# Power-Supply.net
KiCad netlist of a schematic drawn in Altium Designer
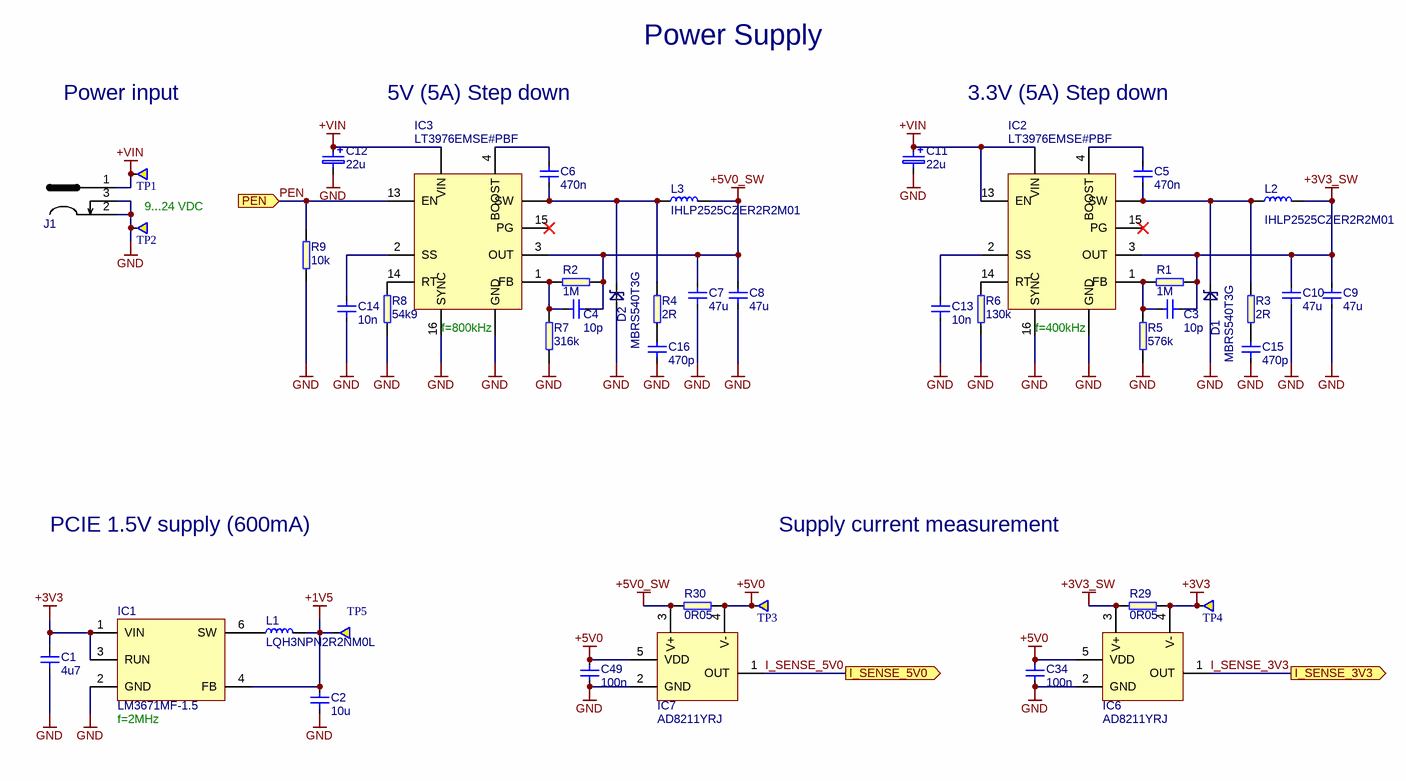
[diagram p0: Power-Supply.SchDoc]

(export (version "E")
  (design (tool "Eeschema 10.0.6"))
  (components
    (comp (ref "C1")
      (value "4u7")
      (footprint "0402")
      (description "MLCC SMT Capacitor 4.7uF 0402")
      (fields (field (name "MANUFACTURER") "MURATA") (field (name "PART NUMBER") "C_4u7_0402"))
      (libsource (lib "TK1Baseboard") (part "C_4u7_0402"))
    )
    (comp (ref "C2")
      (value "10u")
      (footprint "0603")
      (description "MLCC SMT Capacitor 10uF 0603")
      (fields (field (name "MANUFACTURER") "Walsin") (field (name "PART NUMBER") "C_10u_0603"))
      (libsource (lib "TK1Baseboard") (part "C_10u_0603"))
    )
    (comp (ref "C3")
      (value "10p")
      (footprint "0402")
      (description "MLCC SMT Capacitor 10pF 0402")
      (fields (field (name "MANUFACTURER") "MULTICOMP") (field (name "PART NUMBER") "C_10p_0402"))
      (libsource (lib "TK1Baseboard") (part "C_10p_0402"))
    )
    (comp (ref "C4")
      (value "10p")
      (footprint "0402")
      (description "MLCC SMT Capacitor 10pF 0402")
      (fields (field (name "MANUFACTURER") "MULTICOMP") (field (name "PART NUMBER") "C_10p_0402"))
      (libsource (lib "TK1Baseboard") (part "C_10p_0402"))
    )
    (comp (ref "C5")
      (value "470n")
      (footprint "0402")
      (description "MLCC SMT Capacitor 470n 0402")
      (fields (field (name "MANUFACTURER") "TDK") (field (name "PART NUMBER") "C_470n_0402"))
      (libsource (lib "TK1Baseboard") (part "C_470n_0402"))
    )
    (comp (ref "C6")
      (value "470n")
      (footprint "0402")
      (description "MLCC SMT Capacitor 470n 0402")
      (fields (field (name "MANUFACTURER") "TDK") (field (name "PART NUMBER") "C_470n_0402"))
      (libsource (lib "TK1Baseboard") (part "C_470n_0402"))
    )
    (comp (ref "C7")
      (value "47u")
      (footprint "1206")
      (description "MLCC SMT Capacitor 47uF 1206")
      (fields (field (name "MANUFACTURER") "MURATA") (field (name "PART NUMBER") "C_47u_1206"))
      (libsource (lib "TK1Baseboard") (part "C_47u_1206"))
    )
    (comp (ref "C8")
      (value "47u")
      (footprint "1206")
      (description "MLCC SMT Capacitor 47uF 1206")
      (fields (field (name "MANUFACTURER") "MURATA") (field (name "PART NUMBER") "C_47u_1206"))
      (libsource (lib "TK1Baseboard") (part "C_47u_1206"))
    )
    (comp (ref "C9")
      (value "47u")
      (footprint "1206")
      (description "MLCC SMT Capacitor 47uF 1206")
      (fields (field (name "MANUFACTURER") "MURATA") (field (name "PART NUMBER") "C_47u_1206"))
      (libsource (lib "TK1Baseboard") (part "C_47u_1206"))
    )
    (comp (ref "C10")
      (value "47u")
      (footprint "1206")
      (description "MLCC SMT Capacitor 47uF 1206")
      (fields (field (name "MANUFACTURER") "MURATA") (field (name "PART NUMBER") "C_47u_1206"))
      (libsource (lib "TK1Baseboard") (part "C_47u_1206"))
    )
    (comp (ref "C11")
      (value "22u")
      (footprint "KEMET_C")
      (description "Tantalum SMT Capacitor 22uF Case KEMET_C")
      (fields (field (name "PART NUMBER") "C_22u_KEMET_C") (field (name "MANUFACTURER") "KEMET"))
      (libsource (lib "TK1Baseboard") (part "C_22u_KEMET_C"))
    )
    (comp (ref "C12")
      (value "22u")
      (footprint "KEMET_C")
      (description "Tantalum SMT Capacitor 22uF Case KEMET_C")
      (fields (field (name "PART NUMBER") "C_22u_KEMET_C") (field (name "MANUFACTURER") "KEMET"))
      (libsource (lib "TK1Baseboard") (part "C_22u_KEMET_C"))
    )
    (comp (ref "C13")
      (value "10n")
      (footprint "0402")
      (description "MLCC SMT Capacitor 10 nF 0402")
      (fields (field (name "MANUFACTURER") "AVX") (field (name "PART NUMBER") "C_10n_0402"))
      (libsource (lib "TK1Baseboard") (part "C_10n_0402"))
    )
    (comp (ref "C14")
      (value "10n")
      (footprint "0402")
      (description "MLCC SMT Capacitor 10 nF 0402")
      (fields (field (name "MANUFACTURER") "AVX") (field (name "PART NUMBER") "C_10n_0402"))
      (libsource (lib "TK1Baseboard") (part "C_10n_0402"))
    )
    (comp (ref "C15")
      (value "470p")
      (footprint "0402")
      (description "MLCC SMT Capacitor 470pF 0402")
      (fields (field (name "MANUFACTURER") "MULTICOMP") (field (name "PART NUMBER") "C_470p_0402"))
      (libsource (lib "TK1Baseboard") (part "C_470p_0402"))
    )
    (comp (ref "C16")
      (value "470p")
      (footprint "0402")
      (description "MLCC SMT Capacitor 470pF 0402")
      (fields (field (name "MANUFACTURER") "MULTICOMP") (field (name "PART NUMBER") "C_470p_0402"))
      (libsource (lib "TK1Baseboard") (part "C_470p_0402"))
    )
    (comp (ref "C34")
      (value "100n")
      (footprint "0402")
      (description "MLCC SMT Capacitor 100n 0402")
      (fields (field (name "MANUFACTURER") "TDK") (field (name "PART NUMBER") "C_100n_0402"))
      (libsource (lib "TK1Baseboard") (part "C_100n_0402"))
    )
    (comp (ref "C49")
      (value "100n")
      (footprint "0402")
      (description "MLCC SMT Capacitor 100n 0402")
      (fields (field (name "MANUFACTURER") "TDK") (field (name "PART NUMBER") "C_100n_0402"))
      (libsource (lib "TK1Baseboard") (part "C_100n_0402"))
    )
    (comp (ref "D1")
      (value "MBRS540T3G")
      (footprint "SMC-403-03")
      (description "ON SEMICONDUCTOR  MBRS540T3G  Rectifier Diode, Single, 40 V, 5 A, 500 mV, 190 A, 150 °C")
      (fields (field (name "MANUFACTURER") "ON SEMICONDUCTOR"))
      (libsource (lib "TK1Baseboard") (part "MBRS540T3G"))
    )
    (comp (ref "D2")
      (value "MBRS540T3G")
      (footprint "SMC-403-03")
      (description "ON SEMICONDUCTOR  MBRS540T3G  Rectifier Diode, Single, 40 V, 5 A, 500 mV, 190 A, 150 °C")
      (fields (field (name "MANUFACTURER") "ON SEMICONDUCTOR"))
      (libsource (lib "TK1Baseboard") (part "MBRS540T3G"))
    )
    (comp (ref "IC1")
      (value "LM3671MF-1.5")
      (footprint "SOT23-5N")
      (description "DC/DC Buck Converter")
      (fields (field (name "MANUFACTURER") "TEXAS INSTRUMENTS") (field (name "MPN") "LM3671MF-1.5/NOPB"))
      (libsource (lib "TK1Baseboard") (part "LM3671"))
    )
    (comp (ref "IC2")
      (value "LT3976EMSE#PBF")
      (footprint "LT3976EMSE")
      (description "LINEAR TECHNOLOGY  LT3976EMSE#PBF  DC-DC CONVERTER, 2MHZ, 5A, MSOP-16")
      (fields (field (name "MANUFACTURER") "LINEAR TECHNOLOGY"))
      (libsource (lib "TK1Baseboard") (part "LT3976"))
    )
    (comp (ref "IC3")
      (value "LT3976EMSE#PBF")
      (footprint "LT3976EMSE")
      (description "LINEAR TECHNOLOGY  LT3976EMSE#PBF  DC-DC CONVERTER, 2MHZ, 5A, MSOP-16")
      (fields (field (name "MANUFACTURER") "LINEAR TECHNOLOGY"))
      (libsource (lib "TK1Baseboard") (part "LT3976"))
    )
    (comp (ref "IC6")
      (value "AD8211YRJ")
      (footprint "SOT23-5")
      (description "Current Sense Amplifier, High Voltage, 1 Amplifier, SOT-23, 5 Pins, -40 °C, 125 °C")
      (fields (field (name "MANUFACTURER") "ANALOG DEVICES"))
      (libsource (lib "TK1Baseboard") (part "AD8211YRJ"))
    )
    (comp (ref "IC7")
      (value "AD8211YRJ")
      (footprint "SOT23-5")
      (description "Current Sense Amplifier, High Voltage, 1 Amplifier, SOT-23, 5 Pins, -40 °C, 125 °C")
      (fields (field (name "MANUFACTURER") "ANALOG DEVICES"))
      (libsource (lib "TK1Baseboard") (part "AD8211YRJ"))
    )
    (comp (ref "J1")
      (value "694106106102")
      (footprint "694106106102")
      (description "DC Power Jack Right Angled SMT with 4 soldering pads & pegs WR-DC")
      (fields (field (name "PART NUMBER") "WE-694106106102") (field (name "MANUFACTURER") "WURTH ELEKTRONIK"))
      (libsource (lib "TK1Baseboard") (part "DC_SOCKET_2"))
    )
    (comp (ref "L1")
      (value "LQH3NPN2R2NM0L")
      (footprint "LQH3NPN2R2NM")
      (description "INDUCTOR, 2.2 µH, ± 30%, 1212, 90 MHz, 0.073 ohm")
      (fields (field (name "MANUFACTURER") "MURATA"))
      (libsource (lib "TK1Baseboard") (part "LQH3NPN2R2NM0L"))
    )
    (comp (ref "L2")
      (value "IHLP2525CZER2R2M01")
      (footprint "IHLP-2525CZ-01")
      (fields (field (name "MANUFACTURER") "VISHAY") (field (name "MPN") "IHLP2525CZER3R3M01"))
      (libsource (lib "TK1Baseboard") (part "Inductor SMT"))
    )
    (comp (ref "L3")
      (value "IHLP2525CZER2R2M01")
      (footprint "IHLP-2525CZ-01")
      (fields (field (name "MANUFACTURER") "VISHAY") (field (name "MPN") "IHLP2525CZER3R3M01"))
      (libsource (lib "TK1Baseboard") (part "Inductor SMT"))
    )
    (comp (ref "R1")
      (value "1M")
      (footprint "0402")
      (description "RES, 1M, 0402")
      (fields (field (name "MANUFACTURER") "VISHAY") (field (name "PART NUMBER") "R_1M_0402"))
      (libsource (lib "TK1Baseboard") (part "R_1M_0402"))
    )
    (comp (ref "R2")
      (value "1M")
      (footprint "0402")
      (description "RES, 1M, 0402")
      (fields (field (name "MANUFACTURER") "VISHAY") (field (name "PART NUMBER") "R_1M_0402"))
      (libsource (lib "") (part "R_1M_0402_1"))
    )
    (comp (ref "R3")
      (value "2R")
      (footprint "0402")
      (description "RES, 2R, 0402")
      (fields (field (name "MANUFACTURER") "YAGEO") (field (name "PART NUMBER") "R_2R_0402"))
      (libsource (lib "TK1Baseboard") (part "R_2R_0402"))
    )
    (comp (ref "R4")
      (value "2R")
      (footprint "0402")
      (description "RES, 2R, 0402")
      (fields (field (name "MANUFACTURER") "YAGEO") (field (name "PART NUMBER") "R_2R_0402"))
      (libsource (lib "TK1Baseboard") (part "R_2R_0402"))
    )
    (comp (ref "R5")
      (value "576k")
      (footprint "0402")
      (description "RES, 576k, 0402")
      (fields (field (name "MANUFACTURER") "MULTICOMP") (field (name "PART NUMBER") "R_576k_0402"))
      (libsource (lib "TK1Baseboard") (part "R_576k_0402"))
    )
    (comp (ref "R6")
      (value "130k")
      (footprint "0402")
      (description "RES, 130k, 0402")
      (fields (field (name "MANUFACTURER") "MULTICOMP") (field (name "PART NUMBER") "R_130k_0402"))
      (libsource (lib "TK1Baseboard") (part "R_130k_0402"))
    )
    (comp (ref "R7")
      (value "316k")
      (footprint "0402")
      (description "RES, 316k, 0402")
      (fields (field (name "MANUFACTURER") "VISHAY") (field (name "PART NUMBER") "R_316k_0402"))
      (libsource (lib "TK1Baseboard") (part "R_316k_0402"))
    )
    (comp (ref "R8")
      (value "54k9")
      (footprint "0402")
      (description "RES, 54k9, 0402")
      (fields (field (name "MANUFACTURER") "MULTICOMP") (field (name "PART NUMBER") "R_54k9_0402"))
      (libsource (lib "TK1Baseboard") (part "R_54k9_0402"))
    )
    (comp (ref "R9")
      (value "10k")
      (footprint "0402")
      (description "RES, 10k, 0402")
      (fields (field (name "MANUFACTURER") "MULTICOMP") (field (name "PART NUMBER") "R_10k_0402"))
      (libsource (lib "TK1Baseboard") (part "R_10k_0402"))
    )
    (comp (ref "R29")
      (value "0R05")
      (footprint "1206")
      (description "RES, 0R05, 1206")
      (fields (field (name "MANUFACTURER") "PANASONIC") (field (name "PART NUMBER") "R_0R05_1206"))
      (libsource (lib "TK1Baseboard") (part "R_0R05_1206"))
    )
    (comp (ref "R30")
      (value "0R05")
      (footprint "1206")
      (description "RES, 0R05, 1206")
      (fields (field (name "MANUFACTURER") "PANASONIC") (field (name "PART NUMBER") "R_0R05_1206"))
      (libsource (lib "TK1Baseboard") (part "R_0R05_1206"))
    )
    (comp (ref "TP1")
      (value "TP-R-1.5")
      (footprint "TP-R-1.5")
      (description "Testpad, round, 1.5mm")
      (libsource (lib "TK1Baseboard") (part "TP-R-1.5"))
    )
    (comp (ref "TP2")
      (value "TP-R-1.5")
      (footprint "TP-R-1.5")
      (description "Testpad, round, 1.5mm")
      (libsource (lib "TK1Baseboard") (part "TP-R-1.5"))
    )
    (comp (ref "TP3")
      (value "TP-R-1.5")
      (footprint "TP-R-1.5")
      (description "Testpad, round, 1.5mm")
      (libsource (lib "TK1Baseboard") (part "TP-R-1.5"))
    )
    (comp (ref "TP4")
      (value "TP-R-1.5")
      (footprint "TP-R-1.5")
      (description "Testpad, round, 1.5mm")
      (libsource (lib "TK1Baseboard") (part "TP-R-1.5"))
    )
    (comp (ref "TP5")
      (value "TP-R-1.5")
      (footprint "TP-R-1.5")
      (description "Testpad, round, 1.5mm")
      (libsource (lib "TK1Baseboard") (part "TP-R-1.5"))
    )
  )
  (nets
    (net (code "1") (name "+1V5") (class "Default")
      (node (ref "C2") (pin "2") (pinfunction "2_2") (pintype "passive"))
      (node (ref "IC1") (pin "4") (pinfunction "FB_4") (pintype "passive"))
      (node (ref "L1") (pin "2") (pintype "passive"))
      (node (ref "TP5") (pin "1") (pintype "passive"))
    )
    (net (code "2") (name "+3V3") (class "Default")
      (node (ref "C1") (pin "2") (pinfunction "2_2") (pintype "passive"))
      (node (ref "IC1") (pin "1") (pinfunction "VIN_1") (pintype "passive"))
      (node (ref "IC1") (pin "3") (pinfunction "RUN_3") (pintype "passive"))
      (node (ref "IC6") (pin "4") (pinfunction "V-_4") (pintype "passive"))
      (node (ref "R29") (pin "1") (pintype "passive"))
      (node (ref "TP4") (pin "1") (pintype "passive"))
    )
    (net (code "3") (name "+3V3_SW") (class "Default")
      (node (ref "C10") (pin "2") (pinfunction "2_2") (pintype "passive"))
      (node (ref "C3") (pin "1") (pinfunction "1_1") (pintype "passive"))
      (node (ref "C9") (pin "2") (pinfunction "2_2") (pintype "passive"))
      (node (ref "IC2") (pin "3") (pinfunction "OUT_3") (pintype "passive"))
      (node (ref "IC6") (pin "3") (pinfunction "V+_3") (pintype "passive"))
      (node (ref "L2") (pin "2") (pintype "passive"))
      (node (ref "R1") (pin "1") (pintype "passive"))
      (node (ref "R29") (pin "2") (pintype "passive"))
    )
    (net (code "4") (name "+5V0") (class "Default")
      (node (ref "C34") (pin "1") (pinfunction "1_1") (pintype "passive"))
      (node (ref "C49") (pin "1") (pinfunction "1_1") (pintype "passive"))
      (node (ref "IC6") (pin "5") (pinfunction "VDD_5") (pintype "passive"))
      (node (ref "IC7") (pin "4") (pinfunction "V-_4") (pintype "passive"))
      (node (ref "IC7") (pin "5") (pinfunction "VDD_5") (pintype "passive"))
      (node (ref "R30") (pin "1") (pintype "passive"))
      (node (ref "TP3") (pin "1") (pintype "passive"))
    )
    (net (code "5") (name "+5V0_SW") (class "Default")
      (node (ref "C4") (pin "1") (pinfunction "1_1") (pintype "passive"))
      (node (ref "C7") (pin "2") (pinfunction "2_2") (pintype "passive"))
      (node (ref "C8") (pin "2") (pinfunction "2_2") (pintype "passive"))
      (node (ref "IC3") (pin "3") (pinfunction "OUT_3") (pintype "passive"))
      (node (ref "IC7") (pin "3") (pinfunction "V+_3") (pintype "passive"))
      (node (ref "L3") (pin "2") (pintype "passive"))
      (node (ref "R2") (pin "1") (pintype "passive"))
      (node (ref "R30") (pin "2") (pintype "passive"))
    )
    (net (code "6") (name "+VIN") (class "Default")
      (node (ref "C11") (pin "1") (pinfunction "1_1") (pintype "passive"))
      (node (ref "C12") (pin "1") (pinfunction "1_1") (pintype "passive"))
      (node (ref "IC2") (pin "13") (pinfunction "EN_13") (pintype "passive"))
      (node (ref "IC2") (pin "VIN") (pinfunction "VIN_VIN") (pintype "passive"))
      (node (ref "IC3") (pin "VIN") (pinfunction "VIN_VIN") (pintype "passive"))
      (node (ref "J1") (pin "1") (pinfunction "1_1") (pintype "passive"))
      (node (ref "TP1") (pin "1") (pintype "passive"))
    )
    (net (code "7") (name "/I_SENSE_3V3") (class "Default")
      (node (ref "IC6") (pin "1") (pinfunction "OUT_1") (pintype "passive"))
    )
    (net (code "8") (name "/I_SENSE_5V0") (class "Default")
      (node (ref "IC7") (pin "1") (pinfunction "OUT_1") (pintype "passive"))
    )
    (net (code "9") (name "/PEN") (class "Default")
      (node (ref "IC3") (pin "13") (pinfunction "EN_13") (pintype "passive"))
      (node (ref "R9") (pin "2") (pintype "passive"))
    )
    (net (code "10") (name "GND") (class "Default")
      (node (ref "C1") (pin "1") (pinfunction "1_1") (pintype "passive"))
      (node (ref "C10") (pin "1") (pinfunction "1_1") (pintype "passive"))
      (node (ref "C11") (pin "2") (pinfunction "2_2") (pintype "passive"))
      (node (ref "C12") (pin "2") (pinfunction "2_2") (pintype "passive"))
      (node (ref "C13") (pin "1") (pinfunction "1_1") (pintype "passive"))
      (node (ref "C14") (pin "1") (pinfunction "1_1") (pintype "passive"))
      (node (ref "C15") (pin "1") (pinfunction "1_1") (pintype "passive"))
      (node (ref "C16") (pin "1") (pinfunction "1_1") (pintype "passive"))
      (node (ref "C2") (pin "1") (pinfunction "1_1") (pintype "passive"))
      (node (ref "C34") (pin "2") (pinfunction "2_2") (pintype "passive"))
      (node (ref "C49") (pin "2") (pinfunction "2_2") (pintype "passive"))
      (node (ref "C7") (pin "1") (pinfunction "1_1") (pintype "passive"))
      (node (ref "C8") (pin "1") (pinfunction "1_1") (pintype "passive"))
      (node (ref "C9") (pin "1") (pinfunction "1_1") (pintype "passive"))
      (node (ref "D1") (pin "A") (pinfunction "A_A") (pintype "passive"))
      (node (ref "D2") (pin "A") (pinfunction "A_A") (pintype "passive"))
      (node (ref "IC1") (pin "2") (pinfunction "GND_2") (pintype "passive"))
      (node (ref "IC2") (pin "16") (pinfunction "SYNC_16") (pintype "passive"))
      (node (ref "IC2") (pin "GND") (pinfunction "GND_GND") (pintype "passive"))
      (node (ref "IC3") (pin "16") (pinfunction "SYNC_16") (pintype "passive"))
      (node (ref "IC3") (pin "GND") (pinfunction "GND_GND") (pintype "passive"))
      (node (ref "IC6") (pin "2") (pinfunction "GND_2") (pintype "passive"))
      (node (ref "IC7") (pin "2") (pinfunction "GND_2") (pintype "passive"))
      (node (ref "J1") (pin "2") (pinfunction "2_2") (pintype "passive"))
      (node (ref "J1") (pin "3") (pinfunction "3_3") (pintype "passive"))
      (node (ref "R5") (pin "1") (pintype "passive"))
      (node (ref "R6") (pin "1") (pintype "passive"))
      (node (ref "R7") (pin "1") (pintype "passive"))
      (node (ref "R8") (pin "1") (pintype "passive"))
      (node (ref "R9") (pin "1") (pintype "passive"))
      (node (ref "TP2") (pin "1") (pintype "passive"))
    )
    (net (code "11") (name "Net-(C5-Pad1)") (class "Default")
      (node (ref "C5") (pin "1") (pinfunction "1_1") (pintype "passive"))
      (node (ref "D1") (pin "C") (pinfunction "C_C") (pintype "passive"))
      (node (ref "IC2") (pin "SW") (pinfunction "SW_SW") (pintype "passive"))
      (node (ref "L2") (pin "1") (pintype "passive"))
      (node (ref "R3") (pin "2") (pintype "passive"))
    )
    (net (code "12") (name "Net-(C6-Pad1)") (class "Default")
      (node (ref "C6") (pin "1") (pinfunction "1_1") (pintype "passive"))
      (node (ref "D2") (pin "C") (pinfunction "C_C") (pintype "passive"))
      (node (ref "IC3") (pin "SW") (pinfunction "SW_SW") (pintype "passive"))
      (node (ref "L3") (pin "1") (pintype "passive"))
      (node (ref "R4") (pin "2") (pintype "passive"))
    )
    (net (code "13") (name "Net-(C15-Pad2)") (class "Default")
      (node (ref "C15") (pin "2") (pinfunction "2_2") (pintype "passive"))
      (node (ref "R3") (pin "1") (pintype "passive"))
    )
    (net (code "14") (name "Net-(C16-Pad2)") (class "Default")
      (node (ref "C16") (pin "2") (pinfunction "2_2") (pintype "passive"))
      (node (ref "R4") (pin "1") (pintype "passive"))
    )
    (net (code "15") (name "Net-(IC1-SW)") (class "Default")
      (node (ref "IC1") (pin "6") (pinfunction "SW_6") (pintype "passive"))
      (node (ref "L1") (pin "1") (pintype "passive"))
    )
    (net (code "16") (name "Net-(IC2-BOOST)") (class "Default")
      (node (ref "C5") (pin "2") (pinfunction "2_2") (pintype "passive"))
      (node (ref "IC2") (pin "4") (pinfunction "BOOST_4") (pintype "passive"))
    )
    (net (code "17") (name "Net-(IC2-FB)") (class "Default")
      (node (ref "C3") (pin "2") (pinfunction "2_2") (pintype "passive"))
      (node (ref "IC2") (pin "1") (pinfunction "FB_1") (pintype "passive"))
      (node (ref "R1") (pin "2") (pintype "passive"))
      (node (ref "R5") (pin "2") (pintype "passive"))
    )
    (net (code "18") (name "Net-(IC2-RT)") (class "Default")
      (node (ref "IC2") (pin "14") (pinfunction "RT_14") (pintype "passive"))
      (node (ref "R6") (pin "2") (pintype "passive"))
    )
    (net (code "19") (name "Net-(IC2-SS)") (class "Default")
      (node (ref "C13") (pin "2") (pinfunction "2_2") (pintype "passive"))
      (node (ref "IC2") (pin "2") (pinfunction "SS_2") (pintype "passive"))
    )
    (net (code "20") (name "Net-(IC3-BOOST)") (class "Default")
      (node (ref "C6") (pin "2") (pinfunction "2_2") (pintype "passive"))
      (node (ref "IC3") (pin "4") (pinfunction "BOOST_4") (pintype "passive"))
    )
    (net (code "21") (name "Net-(IC3-FB)") (class "Default")
      (node (ref "C4") (pin "2") (pinfunction "2_2") (pintype "passive"))
      (node (ref "IC3") (pin "1") (pinfunction "FB_1") (pintype "passive"))
      (node (ref "R2") (pin "2") (pintype "passive"))
      (node (ref "R7") (pin "2") (pintype "passive"))
    )
    (net (code "22") (name "Net-(IC3-RT)") (class "Default")
      (node (ref "IC3") (pin "14") (pinfunction "RT_14") (pintype "passive"))
      (node (ref "R8") (pin "2") (pintype "passive"))
    )
    (net (code "23") (name "Net-(IC3-SS)") (class "Default")
      (node (ref "C14") (pin "2") (pinfunction "2_2") (pintype "passive"))
      (node (ref "IC3") (pin "2") (pinfunction "SS_2") (pintype "passive"))
    )
    (net (code "24") (name "unconnected-(IC2-PG-Pad15)") (class "Default")
      (node (ref "IC2") (pin "15") (pinfunction "PG_15") (pintype "passive+no_connect"))
    )
    (net (code "25") (name "unconnected-(IC3-PG-Pad15)") (class "Default")
      (node (ref "IC3") (pin "15") (pinfunction "PG_15") (pintype "passive+no_connect"))
    )
  )
)
